# datalogger-v20.net
KiCad netlist of a schematic drawn in EAGLE
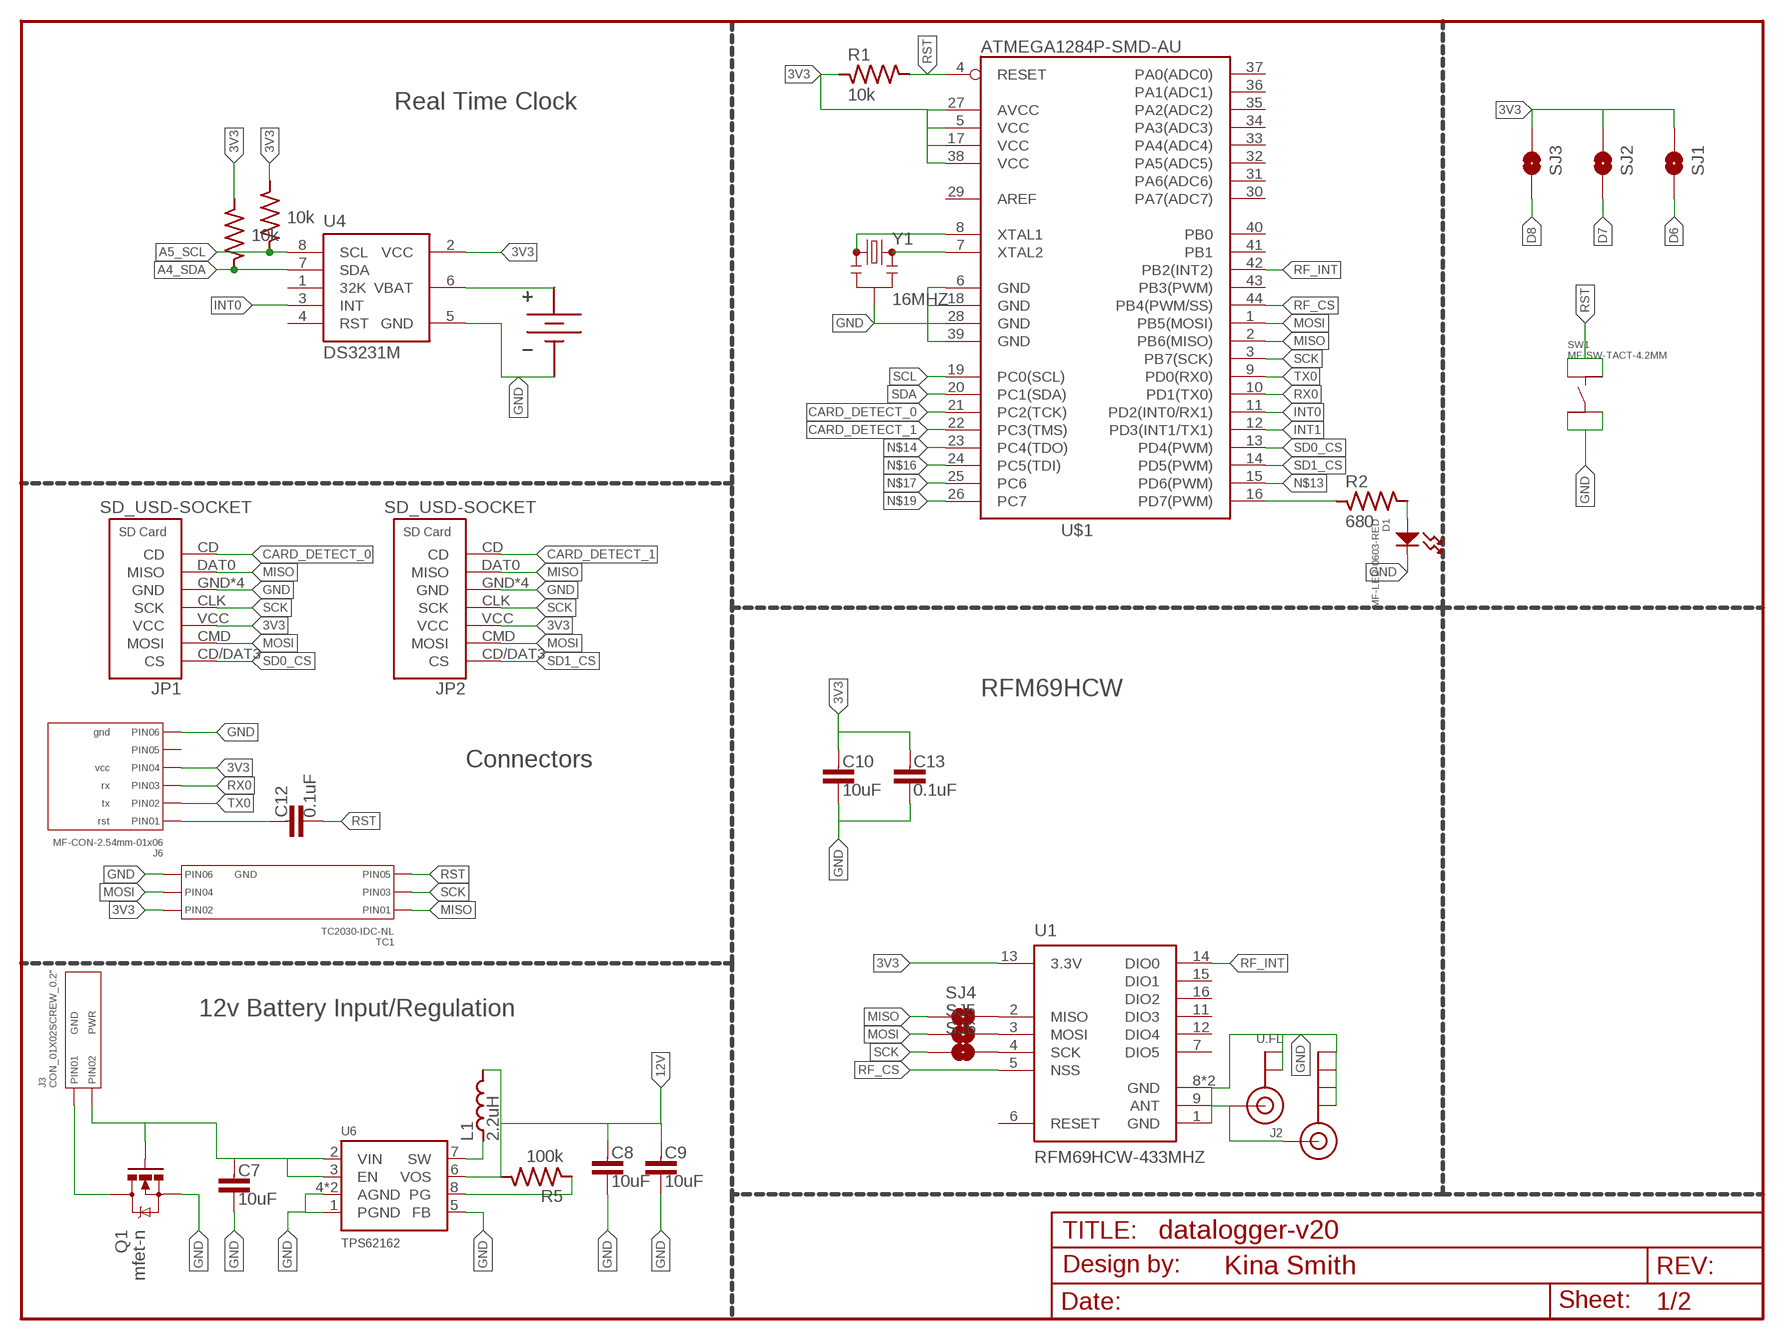
[diagram p0: schematic, sheet 1]
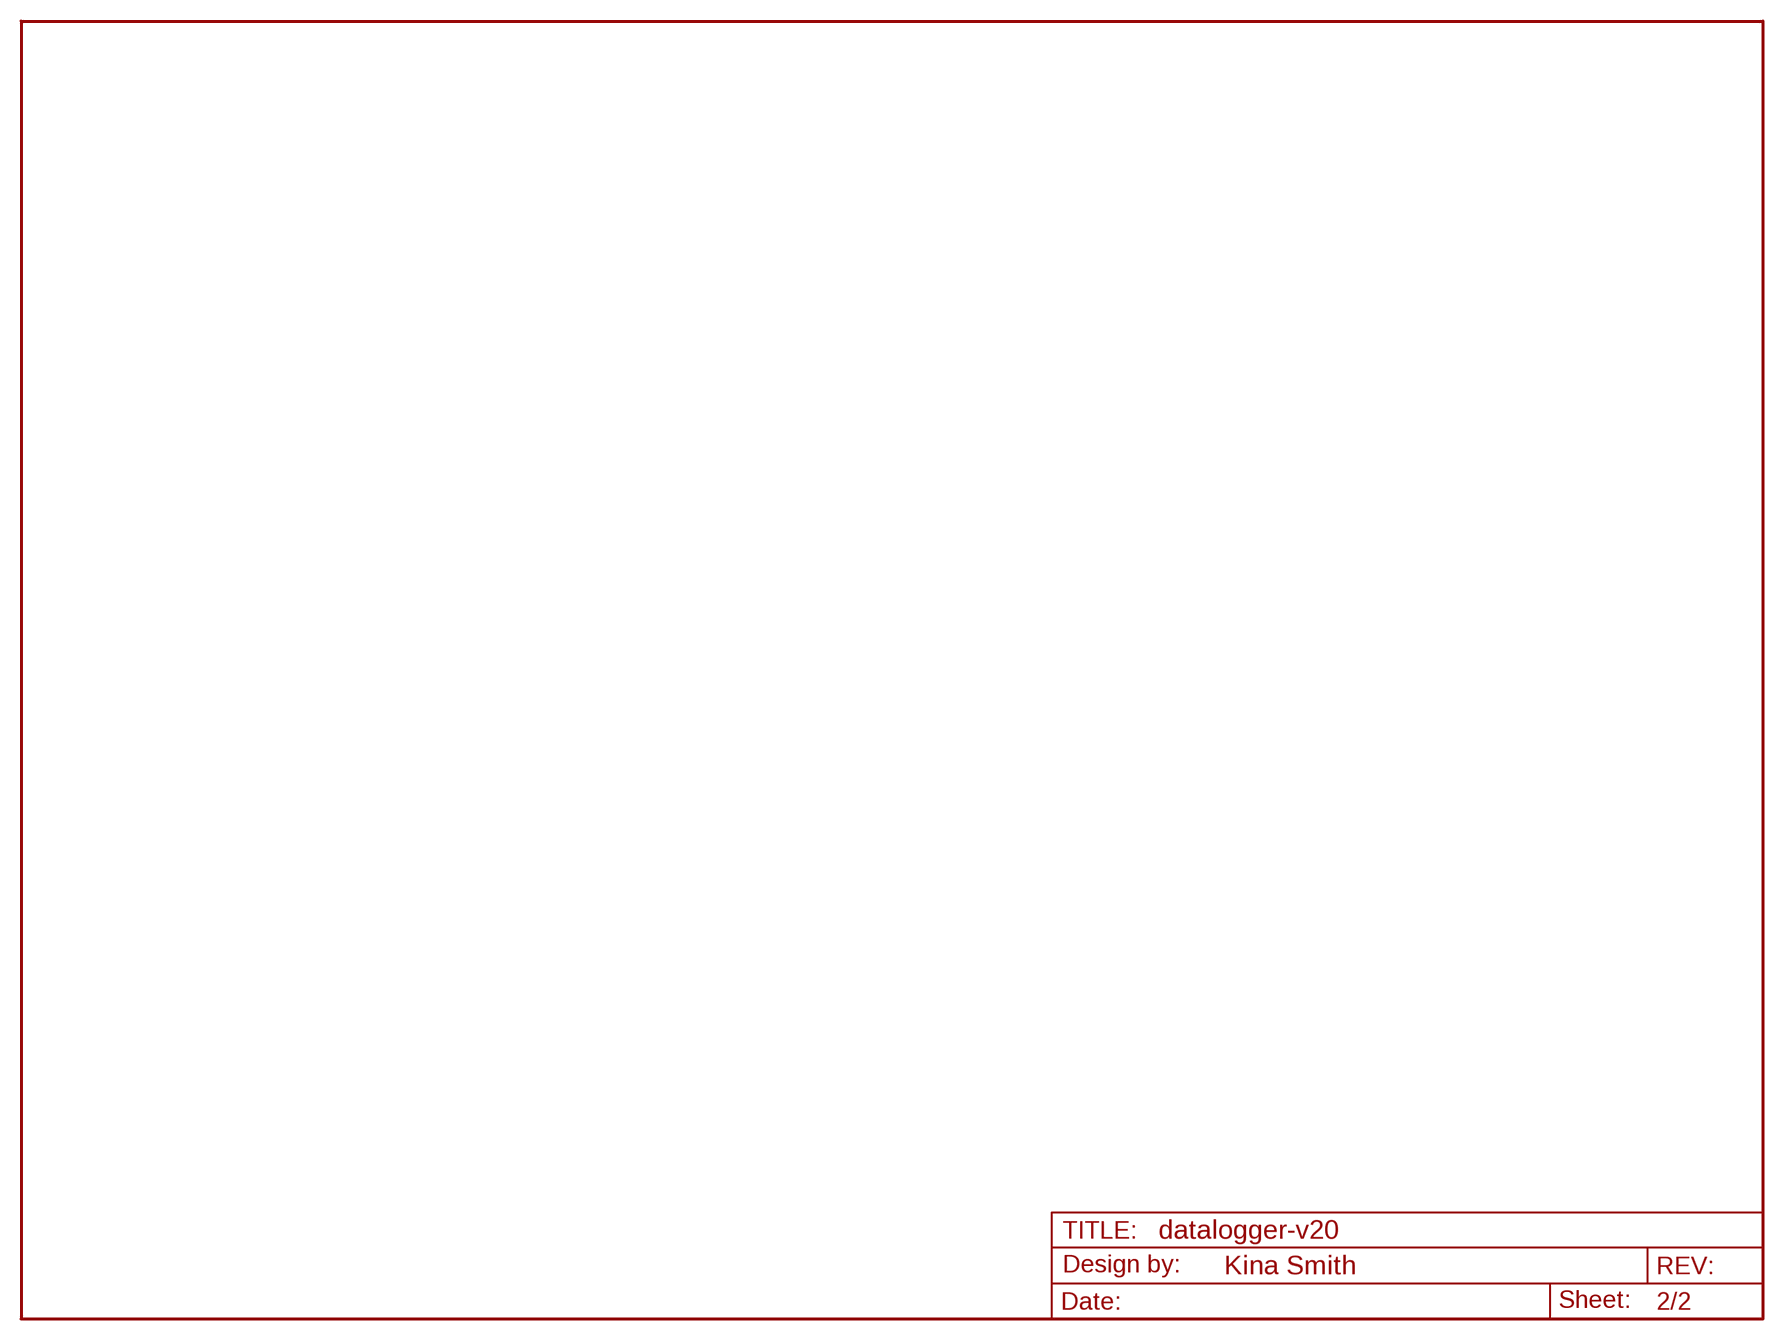
[diagram p1: schematic, sheet 2]

(export (version "E")
  (design (tool "Eeschema 10.0.6"))
  (components
    (comp (ref "FRAME3")
      (value "FRAME-LETTERNO_PACKAGE")
      (footprint "eagle-import:DUMMY")
      (fields (field (name "DESIGNER") "Nobody"))
      (libsource (lib "eagle-import") (part "FRAME-LETTERNO_PACKAGE"))
    )
    (comp (ref "BAT1")
      (value "BATTERY_HOLDER12MM")
      (footprint "eagle-import:BAT_12MM")
      (fields (field (name "PARTNO") "BK-885-TR"))
      (libsource (lib "eagle-import") (part "BATTERY_HOLDER12MM"))
    )
    (comp (ref "C7")
      (value "10uF")
      (footprint "eagle-import:C0805-N")
      (fields (field (name "PARTNO") "GRM21BR61C106KE15L"))
      (libsource (lib "eagle-import") (part "CAPACITOR_NP0805-N"))
    )
    (comp (ref "C8")
      (value "10uF")
      (footprint "eagle-import:C0805-N")
      (fields (field (name "PARTNO") "GRM21BR61C106KE15L"))
      (libsource (lib "eagle-import") (part "CAPACITOR_NP0805-N"))
    )
    (comp (ref "C9")
      (value "10uF")
      (footprint "eagle-import:C0805-N")
      (fields (field (name "PARTNO") "GRM21BR61C106KE15L"))
      (libsource (lib "eagle-import") (part "CAPACITOR_NP0805-N"))
    )
    (comp (ref "C10")
      (value "10uF")
      (footprint "eagle-import:C0805-N")
      (fields (field (name "PARTNO") "GRM21BR61C106KE15L"))
      (libsource (lib "eagle-import") (part "CAPACITOR_NP0805-N"))
    )
    (comp (ref "C12")
      (value "0.1uF")
      (footprint "eagle-import:C0603-N")
      (fields (field (name "PARTNO") "CC0603KRX7R7BB104"))
      (libsource (lib "eagle-import") (part "CAPACITOR_NP0603-N"))
    )
    (comp (ref "C13")
      (value "0.1uF")
      (footprint "eagle-import:C0603-N")
      (fields (field (name "PARTNO") "CC0603KRX7R7BB104"))
      (libsource (lib "eagle-import") (part "CAPACITOR_NP0603-N"))
    )
    (comp (ref "D1")
      (value "MF-LED-0603-RED")
      (footprint "eagle-import:LED0603")
      (fields (field (name "HOUSEPART") "YES"))
      (libsource (lib "eagle-import") (part "LED_SINGLE-0603-RED"))
    )
    (comp (ref "FRAME1")
      (value "FRAME-LETTERNO_PACKAGE")
      (footprint "eagle-import:DUMMY")
      (fields (field (name "DESIGNER") "Nobody"))
      (libsource (lib "eagle-import") (part "FRAME-LETTERNO_PACKAGE"))
    )
    (comp (ref "J2")
      (value "U.FL")
      (footprint "eagle-import:ADAFRUIT_U.FL")
      (fields (field (name "PARTNO") "U.FL-R-SMT-1(10)"))
      (libsource (lib "eagle-import") (part "ANTENNA_U.FL"))
    )
    (comp (ref "J3")
      (value "CON_01X02SCREW_0.2\"")
      (footprint "eagle-import:SCREW_TERM_2POS")
      (fields (field (name "PARTNO") "1729128"))
      (libsource (lib "eagle-import") (part "CON_01X02SCREW_0.2{dblquote}"))
    )
    (comp (ref "J4")
      (value "ANTENNA_SMA_EDGE")
      (footprint "eagle-import:SMA-EDGE")
      (fields (field (name "PARTNO") "EMPCB.SMAFSTJ.B.HT"))
      (libsource (lib "eagle-import") (part "ANTENNA_SMA_EDGE"))
    )
    (comp (ref "J6")
      (value "MF-CON-2.54mm-01x06")
      (footprint "eagle-import:PTH_2.54MM_01X06")
      (fields
        (field (name "HOUSEPART") "YES")
        (field (name "LABEL01") "rst")
        (field (name "LABEL02") "tx")
        (field (name "LABEL03") "rx")
        (field (name "LABEL04") "vcc")
        (field (name "LABEL06") "gnd")
        (field (name "PARTNO") "NA")
      )
      (libsource (lib "eagle-import") (part "CON_01X06_PTH_2.54MM"))
    )
    (comp (ref "JP1")
      (value "SD_USD-SOCKET")
      (footprint "eagle-import:MICRO-SD-SOCKET-SDIO")
      (fields (field (name "PARTNO") "101-00660-68-6"))
      (libsource (lib "eagle-import") (part "SD_USD-SOCKET"))
    )
    (comp (ref "JP2")
      (value "SD_USD-SOCKET")
      (footprint "eagle-import:MICRO-SD-SOCKET-SDIO")
      (fields (field (name "PARTNO") "101-00660-68-6"))
      (libsource (lib "eagle-import") (part "SD_USD-SOCKET"))
    )
    (comp (ref "L1")
      (value "2.2uH")
      (footprint "eagle-import:L2520")
      (fields (field (name "PARTNO") "VLS252012T-2R2M1R3 "))
      (libsource (lib "eagle-import") (part "INDUCTOR2520"))
    )
    (comp (ref "Q1")
      (value "mfet-n")
      (footprint "eagle-import:SOT23-3")
      (fields (field (name "PARTNO") "SI2312BDS-T1-GE3"))
      (libsource (lib "eagle-import") (part "MOSFET-NCHANNELSOT23-3"))
    )
    (comp (ref "R1")
      (value "10k")
      (footprint "eagle-import:R0603-N")
      (fields (field (name "PARTNO") "RC0603FR-0710KL"))
      (libsource (lib "eagle-import") (part "RESISTOR0603-N"))
    )
    (comp (ref "R2")
      (value "680")
      (footprint "eagle-import:R0603-N")
      (fields (field (name "PARTNO") "RC0603FR-0710KL"))
      (libsource (lib "eagle-import") (part "RESISTOR0603-N"))
    )
    (comp (ref "R3")
      (value "10k")
      (footprint "eagle-import:R0603-N")
      (fields (field (name "PARTNO") "RC0603FR-0710KL"))
      (libsource (lib "eagle-import") (part "RESISTOR0603-N"))
    )
    (comp (ref "R4")
      (value "10k")
      (footprint "eagle-import:R0603-N")
      (fields (field (name "PARTNO") "RC0603FR-0710KL"))
      (libsource (lib "eagle-import") (part "RESISTOR0603-N"))
    )
    (comp (ref "R5")
      (value "100k")
      (footprint "eagle-import:R0603-N")
      (fields (field (name "PARTNO") "RC0603FR-07100KL"))
      (libsource (lib "eagle-import") (part "RESISTOR0603-N"))
    )
    (comp (ref "SJ1")
      (value "JUMPER-PAD-2-NOYES_SILK")
      (footprint "eagle-import:PAD-JUMPER-2-NO_YES_SILK")
      (fields (field (name "PARTNO") "NA"))
      (libsource (lib "eagle-import") (part "JUMPER-PAD-2-NOYES_SILK"))
    )
    (comp (ref "SJ2")
      (value "JUMPER-PAD-2-NOYES_SILK")
      (footprint "eagle-import:PAD-JUMPER-2-NO_YES_SILK")
      (fields (field (name "PARTNO") "NA"))
      (libsource (lib "eagle-import") (part "JUMPER-PAD-2-NOYES_SILK"))
    )
    (comp (ref "SJ3")
      (value "JUMPER-PAD-2-NOYES_SILK")
      (footprint "eagle-import:PAD-JUMPER-2-NO_YES_SILK")
      (fields (field (name "PARTNO") "NA"))
      (libsource (lib "eagle-import") (part "JUMPER-PAD-2-NOYES_SILK"))
    )
    (comp (ref "SJ4")
      (value "JUMPER-PAD-2-NOYES_SILK")
      (footprint "eagle-import:PAD-JUMPER-2-NO_YES_SILK")
      (fields (field (name "PARTNO") "NA"))
      (libsource (lib "eagle-import") (part "JUMPER-PAD-2-NOYES_SILK"))
    )
    (comp (ref "SJ5")
      (value "JUMPER-PAD-2-NOYES_SILK")
      (footprint "eagle-import:PAD-JUMPER-2-NO_YES_SILK")
      (fields (field (name "PARTNO") "NA"))
      (libsource (lib "eagle-import") (part "JUMPER-PAD-2-NOYES_SILK"))
    )
    (comp (ref "SJ6")
      (value "JUMPER-PAD-2-NOYES_SILK")
      (footprint "eagle-import:PAD-JUMPER-2-NO_YES_SILK")
      (fields (field (name "PARTNO") "NA"))
      (libsource (lib "eagle-import") (part "JUMPER-PAD-2-NOYES_SILK"))
    )
    (comp (ref "SW1")
      (value "MF-SW-TACT-4.2MM")
      (footprint "eagle-import:TACT4.2MM")
      (fields (field (name "HOUSEPART") "YES") (field (name "PARTNO") "PTS810 SJM 250 SMTR LFS"))
      (libsource (lib "eagle-import") (part "TACT_4.2MM"))
    )
    (comp (ref "TC1")
      (value "TC2030-IDC-NL")
      (footprint "eagle-import:TC2030-IDC-NL")
      (fields (field (name "HOUSEPART") "NO") (field (name "PARTNO") "NA"))
      (libsource (lib "eagle-import") (part "CON_02X03_TC2030-IDC-NL_AVRISP"))
    )
    (comp (ref "U$1")
      (value "ATMEGA1284P-SMD-AU")
      (footprint "eagle-import:TQFP44")
      (libsource (lib "eagle-import") (part "ATMEGA1284P-SMD-AU"))
    )
    (comp (ref "U1")
      (value "RFM69HCW-433MHZ")
      (footprint "eagle-import:RFM69HCW-XXXS2")
      (fields (field (name "PARTNO") "COM-13910"))
      (libsource (lib "eagle-import") (part "RFM69HCW-433MHZ"))
    )
    (comp (ref "U4")
      (value "DS3231M")
      (footprint "eagle-import:SO08")
      (fields (field (name "PARTNO") "DS3231MZ/V+"))
      (libsource (lib "eagle-import") (part "DS3231M"))
    )
    (comp (ref "U6")
      (value "TPS62162")
      (footprint "eagle-import:WSON-8")
      (fields (field (name "PARTNO") "TPS62162DSGR"))
      (libsource (lib "eagle-import") (part "TPS62162"))
    )
    (comp (ref "Y1")
      (value "16MHZ")
      (footprint "eagle-import:RESONATOR-SMD")
      (libsource (lib "eagle-import") (part "RESONATOR16MHZ"))
    )
  )
  (nets
    (net (code "1") (name "3V3") (class "Default")
      (node (ref "C10") (pin "1") (pinfunction "1_1") (pintype "passive"))
      (node (ref "C13") (pin "1") (pinfunction "1_1") (pintype "passive"))
      (node (ref "J6") (pin "P$4") (pinfunction "PIN4_P$4") (pintype "bidirectional"))
      (node (ref "JP1") (pin "VCC") (pinfunction "VCC_VCC") (pintype "bidirectional"))
      (node (ref "JP2") (pin "VCC") (pinfunction "VCC_VCC") (pintype "bidirectional"))
      (node (ref "R1") (pin "1") (pinfunction "P$1_1") (pintype "passive"))
      (node (ref "R3") (pin "2") (pinfunction "P$2_2") (pintype "passive"))
      (node (ref "R4") (pin "2") (pinfunction "P$2_2") (pintype "passive"))
      (node (ref "SJ1") (pin "1") (pinfunction "1_1") (pintype "passive"))
      (node (ref "SJ2") (pin "1") (pinfunction "1_1") (pintype "passive"))
      (node (ref "SJ3") (pin "1") (pinfunction "1_1") (pintype "passive"))
      (node (ref "TC1") (pin "P$2") (pinfunction "PIN2_P$2") (pintype "bidirectional"))
      (node (ref "U$1") (pin "17") (pinfunction "VCC_17") (pintype "bidirectional"))
      (node (ref "U$1") (pin "27") (pinfunction "AVCC_27") (pintype "bidirectional"))
      (node (ref "U$1") (pin "38") (pinfunction "VCC_38") (pintype "bidirectional"))
      (node (ref "U$1") (pin "5") (pinfunction "VCC_5") (pintype "bidirectional"))
      (node (ref "U1") (pin "13") (pinfunction "3.3V_13") (pintype "power_in"))
      (node (ref "U4") (pin "2") (pinfunction "VCC_2") (pintype "power_in"))
    )
    (net (code "2") (name "12V") (class "Default")
      (node (ref "C8") (pin "1") (pinfunction "1_1") (pintype "passive"))
      (node (ref "C9") (pin "1") (pinfunction "1_1") (pintype "passive"))
      (node (ref "L1") (pin "P$2") (pinfunction "P$2_P$2") (pintype "passive"))
      (node (ref "R5") (pin "2") (pinfunction "P$2_2") (pintype "passive"))
      (node (ref "U6") (pin "6") (pinfunction "VOS_6") (pintype "bidirectional"))
    )
    (net (code "3") (name "A4_SDA") (class "Default")
      (node (ref "R4") (pin "1") (pinfunction "P$1_1") (pintype "passive"))
      (node (ref "U4") (pin "7") (pinfunction "SDA_7") (pintype "bidirectional"))
    )
    (net (code "4") (name "A5_SCL") (class "Default")
      (node (ref "R3") (pin "1") (pinfunction "P$1_1") (pintype "passive"))
      (node (ref "U4") (pin "8") (pinfunction "SCL_8") (pintype "bidirectional"))
    )
    (net (code "5") (name "CARD_DETECT_0") (class "Default")
      (node (ref "JP1") (pin "CD") (pinfunction "CD_CD") (pintype "bidirectional"))
      (node (ref "U$1") (pin "21") (pinfunction "PC2(TCK)_21") (pintype "bidirectional"))
    )
    (net (code "6") (name "CARD_DETECT_1") (class "Default")
      (node (ref "JP2") (pin "CD") (pinfunction "CD_CD") (pintype "bidirectional"))
      (node (ref "U$1") (pin "22") (pinfunction "PC3(TMS)_22") (pintype "bidirectional"))
    )
    (net (code "7") (name "D6") (class "Default")
      (node (ref "SJ1") (pin "2") (pinfunction "2_2") (pintype "passive"))
    )
    (net (code "8") (name "D7") (class "Default")
      (node (ref "SJ2") (pin "2") (pinfunction "2_2") (pintype "passive"))
    )
    (net (code "9") (name "D8") (class "Default")
      (node (ref "SJ3") (pin "2") (pinfunction "2_2") (pintype "passive"))
    )
    (net (code "10") (name "GND") (class "Default")
      (node (ref "BAT1") (pin "GND") (pinfunction "GND_GND") (pintype "bidirectional"))
      (node (ref "C10") (pin "2") (pinfunction "2_2") (pintype "passive"))
      (node (ref "C13") (pin "2") (pinfunction "2_2") (pintype "passive"))
      (node (ref "C7") (pin "2") (pinfunction "2_2") (pintype "passive"))
      (node (ref "C8") (pin "2") (pinfunction "2_2") (pintype "passive"))
      (node (ref "C9") (pin "2") (pinfunction "2_2") (pintype "passive"))
      (node (ref "D1") (pin "CATHODE") (pinfunction "CATHODE_CATHODE") (pintype "power_in"))
      (node (ref "J2") (pin "1") (pinfunction "GND_1") (pintype "passive"))
      (node (ref "J2") (pin "2") (pinfunction "GND_2") (pintype "passive"))
      (node (ref "J4") (pin "GND@0") (pinfunction "GND_GND@0") (pintype "bidirectional"))
      (node (ref "J4") (pin "GND@1") (pinfunction "GND_GND@1") (pintype "bidirectional"))
      (node (ref "J4") (pin "GND@2") (pinfunction "GND_GND@2") (pintype "bidirectional"))
      (node (ref "J4") (pin "GND@3") (pinfunction "GND_GND@3") (pintype "bidirectional"))
      (node (ref "J6") (pin "P$6") (pinfunction "PIN6_P$6") (pintype "bidirectional"))
      (node (ref "JP1") (pin "GND") (pinfunction "GND_GND") (pintype "bidirectional"))
      (node (ref "JP1") (pin "GND1") (pinfunction "GND_GND1") (pintype "bidirectional"))
      (node (ref "JP1") (pin "GND2") (pinfunction "GND_GND2") (pintype "bidirectional"))
      (node (ref "JP1") (pin "GND3") (pinfunction "GND_GND3") (pintype "bidirectional"))
      (node (ref "JP2") (pin "GND") (pinfunction "GND_GND") (pintype "bidirectional"))
      (node (ref "JP2") (pin "GND1") (pinfunction "GND_GND1") (pintype "bidirectional"))
      (node (ref "JP2") (pin "GND2") (pinfunction "GND_GND2") (pintype "bidirectional"))
      (node (ref "JP2") (pin "GND3") (pinfunction "GND_GND3") (pintype "bidirectional"))
      (node (ref "Q1") (pin "2") (pinfunction "S_2") (pintype "passive"))
      (node (ref "SW1") (pin "P$3") (pinfunction "P$3_P$3") (pintype "bidirectional"))
      (node (ref "SW1") (pin "P$4") (pinfunction "P$4_P$4") (pintype "bidirectional"))
      (node (ref "TC1") (pin "P$6") (pinfunction "PIN6_P$6") (pintype "bidirectional"))
      (node (ref "U$1") (pin "18") (pinfunction "GND_18") (pintype "bidirectional"))
      (node (ref "U$1") (pin "28") (pinfunction "GND_28") (pintype "bidirectional"))
      (node (ref "U$1") (pin "39") (pinfunction "GND_39") (pintype "bidirectional"))
      (node (ref "U$1") (pin "6") (pinfunction "GND_6") (pintype "bidirectional"))
      (node (ref "U1") (pin "1") (pinfunction "GND_1") (pintype "power_in"))
      (node (ref "U1") (pin "10") (pinfunction "GND_10") (pintype "power_in"))
      (node (ref "U1") (pin "8") (pinfunction "GND_8") (pintype "power_in"))
      (node (ref "U4") (pin "5") (pinfunction "GND_5") (pintype "power_in"))
      (node (ref "U6") (pin "1") (pinfunction "PGND_1") (pintype "bidirectional"))
      (node (ref "U6") (pin "4") (pinfunction "AGND_4") (pintype "bidirectional"))
      (node (ref "U6") (pin "5") (pinfunction "FB_5") (pintype "bidirectional"))
      (node (ref "U6") (pin "P$9") (pinfunction "AGND_P$9") (pintype "bidirectional"))
      (node (ref "Y1") (pin "2") (pinfunction "2_2") (pintype "passive"))
    )
    (net (code "11") (name "INT0") (class "Default")
      (node (ref "U$1") (pin "11") (pinfunction "PD2(INT0/RX1)_11") (pintype "bidirectional"))
      (node (ref "U4") (pin "3") (pinfunction "INT_3") (pintype "bidirectional"))
    )
    (net (code "12") (name "INT1") (class "Default")
      (node (ref "U$1") (pin "12") (pinfunction "PD3(INT1/TX1)_12") (pintype "bidirectional"))
    )
    (net (code "13") (name "MISO") (class "Default")
      (node (ref "JP1") (pin "DAT0") (pinfunction "MISO_DAT0") (pintype "bidirectional"))
      (node (ref "JP2") (pin "DAT0") (pinfunction "MISO_DAT0") (pintype "bidirectional"))
      (node (ref "SJ4") (pin "1") (pinfunction "1_1") (pintype "passive"))
      (node (ref "TC1") (pin "P$1") (pinfunction "PIN1_P$1") (pintype "bidirectional"))
      (node (ref "U$1") (pin "2") (pinfunction "PB6(MISO)_2") (pintype "bidirectional"))
    )
    (net (code "14") (name "MOSI") (class "Default")
      (node (ref "JP1") (pin "CMD") (pinfunction "MOSI_CMD") (pintype "bidirectional"))
      (node (ref "JP2") (pin "CMD") (pinfunction "MOSI_CMD") (pintype "bidirectional"))
      (node (ref "SJ5") (pin "1") (pinfunction "1_1") (pintype "passive"))
      (node (ref "TC1") (pin "P$4") (pinfunction "PIN4_P$4") (pintype "bidirectional"))
      (node (ref "U$1") (pin "1") (pinfunction "PB5(MOSI)_1") (pintype "bidirectional"))
    )
    (net (code "15") (name "N$13") (class "Default")
      (node (ref "U$1") (pin "15") (pinfunction "PD6(PWM)_15") (pintype "bidirectional"))
    )
    (net (code "16") (name "N$14") (class "Default")
      (node (ref "U$1") (pin "23") (pinfunction "PC4(TDO)_23") (pintype "bidirectional"))
    )
    (net (code "17") (name "N$16") (class "Default")
      (node (ref "U$1") (pin "24") (pinfunction "PC5(TDI)_24") (pintype "bidirectional"))
    )
    (net (code "18") (name "N$17") (class "Default")
      (node (ref "U$1") (pin "25") (pinfunction "PC6_25") (pintype "bidirectional"))
    )
    (net (code "19") (name "N$19") (class "Default")
      (node (ref "U$1") (pin "26") (pinfunction "PC7_26") (pintype "bidirectional"))
    )
    (net (code "20") (name "Net-(J2-SIGNAL)") (class "Default")
      (node (ref "J2") (pin "3") (pinfunction "SIGNAL_3") (pintype "passive"))
      (node (ref "J4") (pin "SIG") (pinfunction "SIGNAL_SIG") (pintype "bidirectional"))
      (node (ref "U1") (pin "9") (pinfunction "ANT_9") (pintype "passive"))
    )
    (net (code "21") (name "Net-(J3-PIN1)") (class "Default")
      (node (ref "J3") (pin "GND") (pinfunction "PIN1_GND") (pintype "bidirectional"))
      (node (ref "Q1") (pin "3") (pinfunction "D_3") (pintype "passive"))
    )
    (net (code "22") (name "Net-(J3-PIN2)") (class "Default")
      (node (ref "C7") (pin "1") (pinfunction "1_1") (pintype "passive"))
      (node (ref "J3") (pin "PWR") (pinfunction "PIN2_PWR") (pintype "bidirectional"))
      (node (ref "Q1") (pin "1") (pinfunction "G_1") (pintype "passive"))
      (node (ref "U6") (pin "2") (pinfunction "VIN_2") (pintype "bidirectional"))
      (node (ref "U6") (pin "3") (pinfunction "EN_3") (pintype "bidirectional"))
    )
    (net (code "23") (name "Net-(J6-PIN1)") (class "Default")
      (node (ref "C12") (pin "1") (pinfunction "1_1") (pintype "passive"))
      (node (ref "J6") (pin "P$1") (pinfunction "PIN1_P$1") (pintype "bidirectional"))
    )
    (net (code "24") (name "Net-(R2-P$1)") (class "Default")
      (node (ref "R2") (pin "1") (pinfunction "P$1_1") (pintype "passive"))
      (node (ref "U$1") (pin "16") (pinfunction "PD7(PWM)_16") (pintype "bidirectional"))
    )
    (net (code "25") (name "Net-(R2-P$2)") (class "Default")
      (node (ref "D1") (pin "ANODE") (pinfunction "ANODE_ANODE") (pintype "power_in"))
      (node (ref "R2") (pin "2") (pinfunction "P$2_2") (pintype "passive"))
    )
    (net (code "26") (name "Net-(R5-P$1)") (class "Default")
      (node (ref "R5") (pin "1") (pinfunction "P$1_1") (pintype "passive"))
      (node (ref "U6") (pin "8") (pinfunction "PG_8") (pintype "bidirectional"))
    )
    (net (code "27") (name "Net-(U$1-XTAL1)") (class "Default")
      (node (ref "U$1") (pin "8") (pinfunction "XTAL1_8") (pintype "bidirectional"))
      (node (ref "Y1") (pin "1") (pinfunction "1_1") (pintype "passive"))
    )
    (net (code "28") (name "Net-(U$1-XTAL2)") (class "Default")
      (node (ref "U$1") (pin "7") (pinfunction "XTAL2_7") (pintype "bidirectional"))
      (node (ref "Y1") (pin "3") (pinfunction "3_3") (pintype "passive"))
    )
    (net (code "29") (name "Net-(U1-MISO)") (class "Default")
      (node (ref "SJ4") (pin "2") (pinfunction "2_2") (pintype "passive"))
      (node (ref "U1") (pin "2") (pinfunction "MISO_2") (pintype "bidirectional"))
    )
    (net (code "30") (name "Net-(U1-MOSI)") (class "Default")
      (node (ref "SJ5") (pin "2") (pinfunction "2_2") (pintype "passive"))
      (node (ref "U1") (pin "3") (pinfunction "MOSI_3") (pintype "input"))
    )
    (net (code "31") (name "Net-(U1-SCK)") (class "Default")
      (node (ref "SJ6") (pin "2") (pinfunction "2_2") (pintype "passive"))
      (node (ref "U1") (pin "4") (pinfunction "SCK_4") (pintype "input"))
    )
    (net (code "32") (name "Net-(U4-VBAT)") (class "Default")
      (node (ref "BAT1") (pin "PWR@1") (pinfunction "VBAT_PWR@1") (pintype "bidirectional"))
      (node (ref "BAT1") (pin "PWR@2") (pinfunction "VBAT_PWR@2") (pintype "bidirectional"))
      (node (ref "U4") (pin "6") (pinfunction "VBAT_6") (pintype "power_in"))
    )
    (net (code "33") (name "Net-(U6-SW)") (class "Default")
      (node (ref "L1") (pin "P$1") (pinfunction "P$1_P$1") (pintype "passive"))
      (node (ref "U6") (pin "7") (pinfunction "SW_7") (pintype "bidirectional"))
    )
    (net (code "34") (name "RF_CS") (class "Default")
      (node (ref "U$1") (pin "44") (pinfunction "PB4(PWM/SS)_44") (pintype "bidirectional"))
      (node (ref "U1") (pin "5") (pinfunction "NSS_5") (pintype "input"))
    )
    (net (code "35") (name "RF_INT") (class "Default")
      (node (ref "U$1") (pin "42") (pinfunction "PB2(INT2)_42") (pintype "bidirectional"))
      (node (ref "U1") (pin "14") (pinfunction "DIO0_14") (pintype "bidirectional"))
    )
    (net (code "36") (name "RST") (class "Default")
      (node (ref "C12") (pin "2") (pinfunction "2_2") (pintype "passive"))
      (node (ref "R1") (pin "2") (pinfunction "P$2_2") (pintype "passive"))
      (node (ref "SW1") (pin "P$1") (pinfunction "P$1_P$1") (pintype "bidirectional"))
      (node (ref "SW1") (pin "P$2") (pinfunction "P$2_P$2") (pintype "bidirectional"))
      (node (ref "TC1") (pin "P$5") (pinfunction "PIN5_P$5") (pintype "bidirectional"))
      (node (ref "U$1") (pin "4") (pinfunction "RESET_4") (pintype "bidirectional"))
    )
    (net (code "37") (name "RX0") (class "Default")
      (node (ref "J6") (pin "P$3") (pinfunction "PIN3_P$3") (pintype "bidirectional"))
      (node (ref "U$1") (pin "10") (pinfunction "PD1(TX0)_10") (pintype "bidirectional"))
    )
    (net (code "38") (name "SCK") (class "Default")
      (node (ref "JP1") (pin "CLK") (pinfunction "SCK_CLK") (pintype "bidirectional"))
      (node (ref "JP2") (pin "CLK") (pinfunction "SCK_CLK") (pintype "bidirectional"))
      (node (ref "SJ6") (pin "1") (pinfunction "1_1") (pintype "passive"))
      (node (ref "TC1") (pin "P$3") (pinfunction "PIN3_P$3") (pintype "bidirectional"))
      (node (ref "U$1") (pin "3") (pinfunction "PB7(SCK)_3") (pintype "bidirectional"))
    )
    (net (code "39") (name "SCL") (class "Default")
      (node (ref "U$1") (pin "19") (pinfunction "PC0(SCL)_19") (pintype "bidirectional"))
    )
    (net (code "40") (name "SD0_CS") (class "Default")
      (node (ref "JP1") (pin "CD/DAT3") (pinfunction "CS_CD/DAT3") (pintype "bidirectional"))
      (node (ref "U$1") (pin "13") (pinfunction "PD4(PWM)_13") (pintype "bidirectional"))
    )
    (net (code "41") (name "SD1_CS") (class "Default")
      (node (ref "JP2") (pin "CD/DAT3") (pinfunction "CS_CD/DAT3") (pintype "bidirectional"))
      (node (ref "U$1") (pin "14") (pinfunction "PD5(PWM)_14") (pintype "bidirectional"))
    )
    (net (code "42") (name "SDA") (class "Default")
      (node (ref "U$1") (pin "20") (pinfunction "PC1(SDA)_20") (pintype "bidirectional"))
    )
    (net (code "43") (name "TX0") (class "Default")
      (node (ref "J6") (pin "P$2") (pinfunction "PIN2_P$2") (pintype "bidirectional"))
      (node (ref "U$1") (pin "9") (pinfunction "PD0(RX0)_9") (pintype "bidirectional"))
    )
    (net (code "44") (name "unconnected-(J6-PIN5-PadP$5)") (class "Default")
      (node (ref "J6") (pin "P$5") (pinfunction "PIN5_P$5") (pintype "bidirectional"))
    )
    (net (code "45") (name "unconnected-(U$1-AREF-Pad29)") (class "Default")
      (node (ref "U$1") (pin "29") (pinfunction "AREF_29") (pintype "bidirectional"))
    )
    (net (code "46") (name "unconnected-(U$1-PA0(ADC0)-Pad37)") (class "Default")
      (node (ref "U$1") (pin "37") (pinfunction "PA0(ADC0)_37") (pintype "bidirectional"))
    )
    (net (code "47") (name "unconnected-(U$1-PA1(ADC1)-Pad36)") (class "Default")
      (node (ref "U$1") (pin "36") (pinfunction "PA1(ADC1)_36") (pintype "bidirectional"))
    )
    (net (code "48") (name "unconnected-(U$1-PA2(ADC2)-Pad35)") (class "Default")
      (node (ref "U$1") (pin "35") (pinfunction "PA2(ADC2)_35") (pintype "bidirectional"))
    )
    (net (code "49") (name "unconnected-(U$1-PA3(ADC3)-Pad34)") (class "Default")
      (node (ref "U$1") (pin "34") (pinfunction "PA3(ADC3)_34") (pintype "bidirectional"))
    )
    (net (code "50") (name "unconnected-(U$1-PA4(ADC4)-Pad33)") (class "Default")
      (node (ref "U$1") (pin "33") (pinfunction "PA4(ADC4)_33") (pintype "bidirectional"))
    )
    (net (code "51") (name "unconnected-(U$1-PA5(ADC5)-Pad32)") (class "Default")
      (node (ref "U$1") (pin "32") (pinfunction "PA5(ADC5)_32") (pintype "bidirectional"))
    )
    (net (code "52") (name "unconnected-(U$1-PA6(ADC6)-Pad31)") (class "Default")
      (node (ref "U$1") (pin "31") (pinfunction "PA6(ADC6)_31") (pintype "bidirectional"))
    )
    (net (code "53") (name "unconnected-(U$1-PA7(ADC7)-Pad30)") (class "Default")
      (node (ref "U$1") (pin "30") (pinfunction "PA7(ADC7)_30") (pintype "bidirectional"))
    )
    (net (code "54") (name "unconnected-(U$1-PB0-Pad40)") (class "Default")
      (node (ref "U$1") (pin "40") (pinfunction "PB0_40") (pintype "bidirectional"))
    )
    (net (code "55") (name "unconnected-(U$1-PB1-Pad41)") (class "Default")
      (node (ref "U$1") (pin "41") (pinfunction "PB1_41") (pintype "bidirectional"))
    )
    (net (code "56") (name "unconnected-(U$1-PB3(PWM)-Pad43)") (class "Default")
      (node (ref "U$1") (pin "43") (pinfunction "PB3(PWM)_43") (pintype "bidirectional"))
    )
    (net (code "57") (name "unconnected-(U1-DIO1-Pad15)") (class "Default")
      (node (ref "U1") (pin "15") (pinfunction "DIO1_15") (pintype "bidirectional"))
    )
    (net (code "58") (name "unconnected-(U1-DIO2-Pad16)") (class "Default")
      (node (ref "U1") (pin "16") (pinfunction "DIO2_16") (pintype "bidirectional"))
    )
    (net (code "59") (name "unconnected-(U1-DIO3-Pad11)") (class "Default")
      (node (ref "U1") (pin "11") (pinfunction "DIO3_11") (pintype "bidirectional"))
    )
    (net (code "60") (name "unconnected-(U1-DIO4-Pad12)") (class "Default")
      (node (ref "U1") (pin "12") (pinfunction "DIO4_12") (pintype "bidirectional"))
    )
    (net (code "61") (name "unconnected-(U1-DIO5-Pad7)") (class "Default")
      (node (ref "U1") (pin "7") (pinfunction "DIO5_7") (pintype "bidirectional"))
    )
    (net (code "62") (name "unconnected-(U1-RESET-Pad6)") (class "Default")
      (node (ref "U1") (pin "6") (pinfunction "RESET_6") (pintype "input"))
    )
    (net (code "63") (name "unconnected-(U4-32K-Pad1)") (class "Default")
      (node (ref "U4") (pin "1") (pinfunction "32K_1") (pintype "bidirectional"))
    )
    (net (code "64") (name "unconnected-(U4-RST-Pad4)") (class "Default")
      (node (ref "U4") (pin "4") (pinfunction "RST_4") (pintype "bidirectional"))
    )
  )
)
